# POWER.net
KiCad netlist of a schematic drawn in Altium Designer
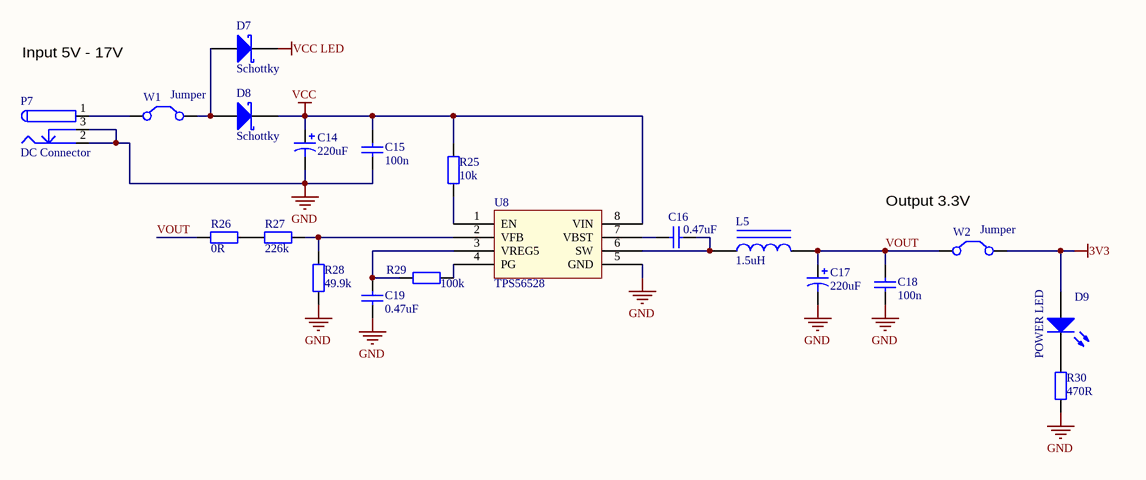
[diagram p0: POWER.SchDoc]

(export (version "E")
  (design (tool "Eeschema 10.0.6"))
  (components
    (comp (ref "C14")
      (value "220uF")
      (footprint "SMD CAPACITOR 220uF")
      (description "Capacitor")
      (fields (field (name "PUBLISHER") "Altium Limited"))
      (libsource (lib "Miscellaneous Devices") (part "Cap Pol1"))
    )
    (comp (ref "C15")
      (value "100n")
      (footprint "1608[0603]")
      (description "Capacitor")
      (fields (field (name "PUBLISHER") "Altium Limited"))
      (libsource (lib "Miscellaneous Devices") (part "Cap"))
    )
    (comp (ref "C16")
      (value "0.47uF")
      (footprint "1608[0603]")
      (description "Capacitor")
      (fields (field (name "PUBLISHER") "Altium Limited"))
      (libsource (lib "Miscellaneous Devices") (part "Cap"))
    )
    (comp (ref "C17")
      (value "220uF")
      (footprint "SMD CAPACITOR 220uF")
      (description "Capacitor")
      (fields (field (name "PUBLISHER") "Altium Limited"))
      (libsource (lib "Miscellaneous Devices") (part "Cap Pol1"))
    )
    (comp (ref "C18")
      (value "100n")
      (footprint "1608[0603]")
      (description "Capacitor")
      (fields (field (name "PUBLISHER") "Altium Limited"))
      (libsource (lib "Miscellaneous Devices") (part "Cap"))
    )
    (comp (ref "C19")
      (value "0.47uF")
      (footprint "1608[0603]")
      (description "Capacitor")
      (fields (field (name "PUBLISHER") "Altium Limited"))
      (libsource (lib "Miscellaneous Devices") (part "Cap"))
    )
    (comp (ref "D7")
      (value "Schottky")
      (footprint "SMB")
      (description "Schottky Diode")
      (fields (field (name "PUBLISHER") "Altium Limited"))
      (libsource (lib "Miscellaneous Devices") (part "D Schottky"))
    )
    (comp (ref "D8")
      (value "Schottky")
      (footprint "SMB")
      (description "Schottky Diode")
      (fields (field (name "PUBLISHER") "Altium Limited"))
      (libsource (lib "Miscellaneous Devices") (part "D Schottky"))
    )
    (comp (ref "D9")
      (value "POWER LED")
      (footprint "LED-1")
      (description "Typical INFRARED GaAs LED")
      (fields (field (name "PUBLISHER") "Altium Limited"))
      (libsource (lib "Miscellaneous Devices") (part "LED0"))
    )
    (comp (ref "L5")
      (value "1.5uH")
      (footprint "Inductor")
      (description "Magnetic-Core Inductor")
      (fields (field (name "PUBLISHER") "Altium Limited"))
      (libsource (lib "Miscellaneous Devices") (part "Inductor Iron"))
    )
    (comp (ref "P7")
      (value "DC Connector")
      (footprint "DC Connector")
      (description "DC Power Connector")
      (libsource (lib "LukaLIBRARY") (part "DC Connector"))
    )
    (comp (ref "R25")
      (value "10k")
      (footprint "1608[0603]")
      (description "Resistor")
      (fields (field (name "PUBLISHER") "Altium Limited"))
      (libsource (lib "") (part "Res2_1"))
    )
    (comp (ref "R26")
      (value "0R")
      (footprint "1608[0603]")
      (description "Resistor")
      (fields (field (name "PUBLISHER") "Altium Limited"))
      (libsource (lib "Miscellaneous Devices") (part "Res2"))
    )
    (comp (ref "R27")
      (value "226k")
      (footprint "1608[0603]")
      (description "Resistor")
      (fields (field (name "PUBLISHER") "Altium Limited"))
      (libsource (lib "Miscellaneous Devices") (part "Res2"))
    )
    (comp (ref "R28")
      (value "49.9k")
      (footprint "1608[0603]")
      (description "Resistor")
      (fields (field (name "PUBLISHER") "Altium Limited"))
      (libsource (lib "") (part "Res2_1"))
    )
    (comp (ref "R29")
      (value "100k")
      (footprint "1608[0603]")
      (description "Resistor")
      (fields (field (name "PUBLISHER") "Altium Limited"))
      (libsource (lib "Miscellaneous Devices") (part "Res2"))
    )
    (comp (ref "R30")
      (value "470R")
      (footprint "1608[0603]")
      (description "Resistor")
      (fields (field (name "PUBLISHER") "Altium Limited"))
      (libsource (lib "") (part "Res2_1"))
    )
    (comp (ref "U8")
      (value "TPS56528")
      (footprint "TPS56528")
      (description "Step-Down Converter 5A 4.5V-18V")
      (libsource (lib "LP_Lib") (part "TPS56528"))
    )
    (comp (ref "W1")
      (value "Jumper")
      (footprint "HDR1X2")
      (description "Jumper Wire")
      (fields (field (name "PUBLISHER") "Altium Limited"))
      (libsource (lib "Miscellaneous Devices") (part "Jumper"))
    )
    (comp (ref "W2")
      (value "Jumper")
      (footprint "HDR1X2")
      (description "Jumper Wire")
      (fields (field (name "PUBLISHER") "Altium Limited"))
      (libsource (lib "Miscellaneous Devices") (part "Jumper"))
    )
  )
  (nets
    (net (code "1") (name "/VOUT") (class "Default")
      (node (ref "C17") (pin "1") (pinfunction "1_1") (pintype "passive"))
      (node (ref "C18") (pin "1") (pinfunction "1_1") (pintype "passive"))
      (node (ref "L5") (pin "2") (pinfunction "2_2") (pintype "passive"))
      (node (ref "R26") (pin "2") (pinfunction "2_2") (pintype "passive"))
      (node (ref "W2") (pin "1") (pinfunction "C1_1") (pintype "passive"))
    )
    (net (code "2") (name "3V3") (class "Default")
      (node (ref "D9") (pin "1") (pinfunction "A_1") (pintype "passive"))
      (node (ref "W2") (pin "2") (pinfunction "C2_2") (pintype "passive"))
    )
    (net (code "3") (name "GND") (class "Default")
      (node (ref "C14") (pin "2") (pinfunction "2_2") (pintype "passive"))
      (node (ref "C15") (pin "2") (pinfunction "2_2") (pintype "passive"))
      (node (ref "C17") (pin "2") (pinfunction "2_2") (pintype "passive"))
      (node (ref "C18") (pin "2") (pinfunction "2_2") (pintype "passive"))
      (node (ref "C19") (pin "2") (pinfunction "2_2") (pintype "passive"))
      (node (ref "P7") (pin "2") (pinfunction "2_2") (pintype "power_in"))
      (node (ref "P7") (pin "3") (pinfunction "3_3") (pintype "power_in"))
      (node (ref "R28") (pin "1") (pinfunction "1_1") (pintype "passive"))
      (node (ref "R30") (pin "1") (pinfunction "1_1") (pintype "passive"))
      (node (ref "U8") (pin "5") (pinfunction "GND_5") (pintype "passive"))
    )
    (net (code "4") (name "Net-(D7-A)") (class "Default")
      (node (ref "D7") (pin "1") (pinfunction "A_1") (pintype "passive"))
      (node (ref "D8") (pin "1") (pinfunction "A_1") (pintype "passive"))
      (node (ref "W1") (pin "2") (pinfunction "C2_2") (pintype "passive"))
    )
    (net (code "5") (name "Net-(D9-K)") (class "Default")
      (node (ref "D9") (pin "2") (pinfunction "K_2") (pintype "passive"))
      (node (ref "R30") (pin "2") (pinfunction "2_2") (pintype "passive"))
    )
    (net (code "6") (name "Net-(R26-Pad1)") (class "Default")
      (node (ref "R26") (pin "1") (pinfunction "1_1") (pintype "passive"))
      (node (ref "R27") (pin "2") (pinfunction "2_2") (pintype "passive"))
    )
    (net (code "7") (name "Net-(U8-EN)") (class "Default")
      (node (ref "R25") (pin "1") (pinfunction "1_1") (pintype "passive"))
      (node (ref "U8") (pin "1") (pinfunction "EN_1") (pintype "passive"))
    )
    (net (code "8") (name "Net-(U8-PG)") (class "Default")
      (node (ref "R29") (pin "1") (pinfunction "1_1") (pintype "passive"))
      (node (ref "U8") (pin "4") (pinfunction "PG_4") (pintype "passive"))
    )
    (net (code "9") (name "Net-(U8-SW)") (class "Default")
      (node (ref "C16") (pin "2") (pinfunction "2_2") (pintype "passive"))
      (node (ref "L5") (pin "1") (pinfunction "1_1") (pintype "passive"))
      (node (ref "U8") (pin "6") (pinfunction "SW_6") (pintype "passive"))
    )
    (net (code "10") (name "Net-(U8-VBST)") (class "Default")
      (node (ref "C16") (pin "1") (pinfunction "1_1") (pintype "passive"))
      (node (ref "U8") (pin "7") (pinfunction "VBST_7") (pintype "passive"))
    )
    (net (code "11") (name "Net-(U8-VFB)") (class "Default")
      (node (ref "R27") (pin "1") (pinfunction "1_1") (pintype "passive"))
      (node (ref "R28") (pin "2") (pinfunction "2_2") (pintype "passive"))
      (node (ref "U8") (pin "2") (pinfunction "VFB_2") (pintype "passive"))
    )
    (net (code "12") (name "Net-(U8-VREG5)") (class "Default")
      (node (ref "C19") (pin "1") (pinfunction "1_1") (pintype "passive"))
      (node (ref "R29") (pin "2") (pinfunction "2_2") (pintype "passive"))
      (node (ref "U8") (pin "3") (pinfunction "VREG5_3") (pintype "passive"))
    )
    (net (code "13") (name "Net-(W1-C1)") (class "Default")
      (node (ref "P7") (pin "1") (pinfunction "1_1") (pintype "power_in"))
      (node (ref "W1") (pin "1") (pinfunction "C1_1") (pintype "passive"))
    )
    (net (code "14") (name "VCC") (class "Default")
      (node (ref "C14") (pin "1") (pinfunction "1_1") (pintype "passive"))
      (node (ref "C15") (pin "1") (pinfunction "1_1") (pintype "passive"))
      (node (ref "D8") (pin "2") (pinfunction "K_2") (pintype "passive"))
      (node (ref "R25") (pin "2") (pinfunction "2_2") (pintype "passive"))
      (node (ref "U8") (pin "8") (pinfunction "VIN_8") (pintype "passive"))
    )
    (net (code "15") (name "VCC LED") (class "Default")
      (node (ref "D7") (pin "2") (pinfunction "K_2") (pintype "passive"))
    )
  )
)
